# PCB_Telemetria_2020.net
KiCad netlist of a schematic drawn in EAGLE
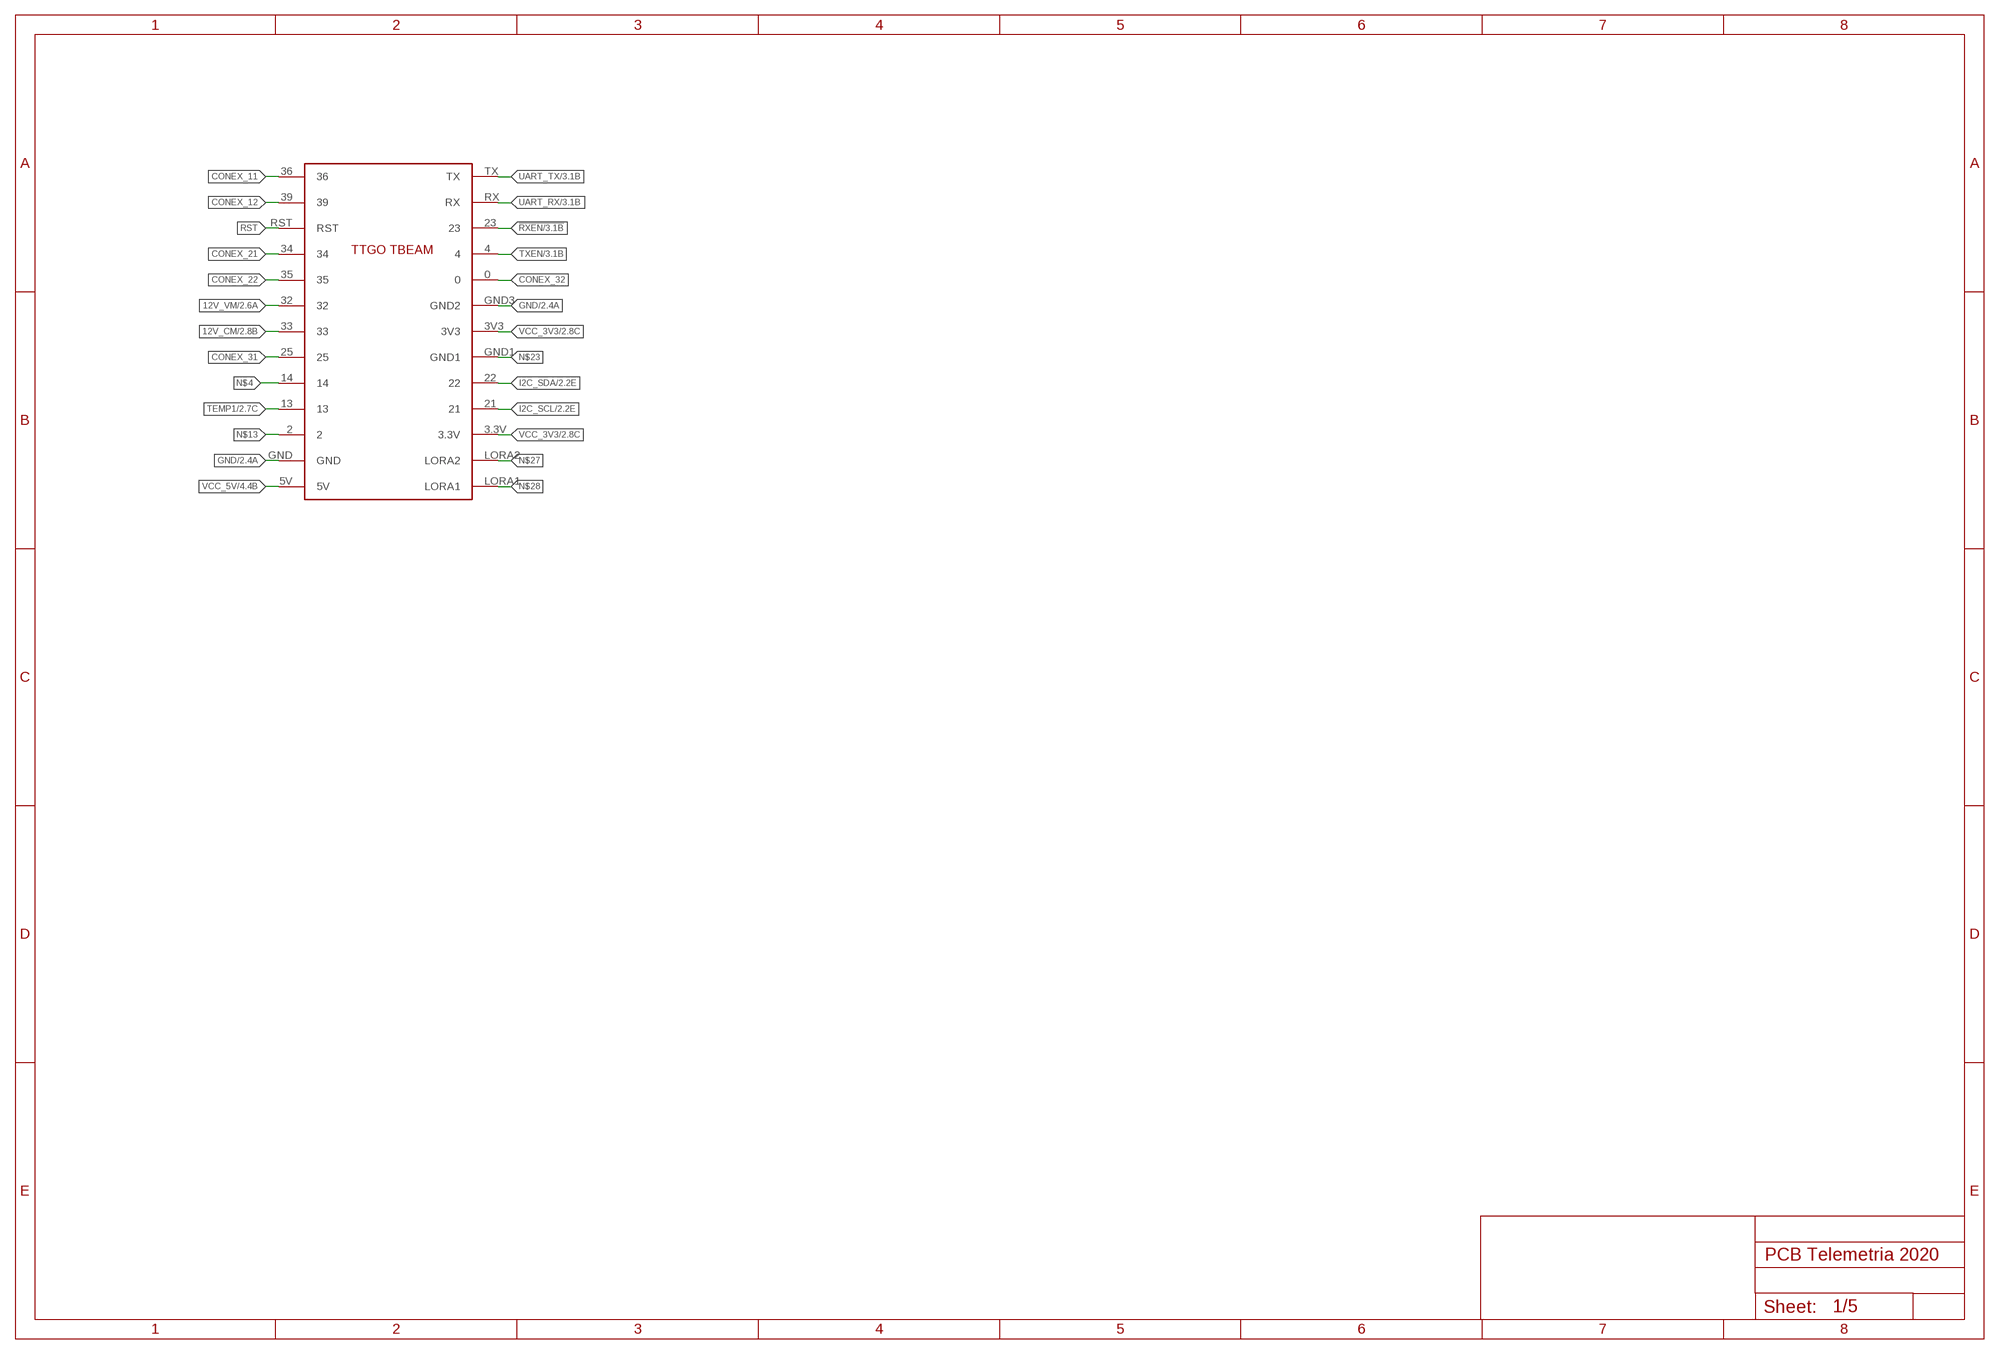
[diagram p0: schematic, sheet 1]
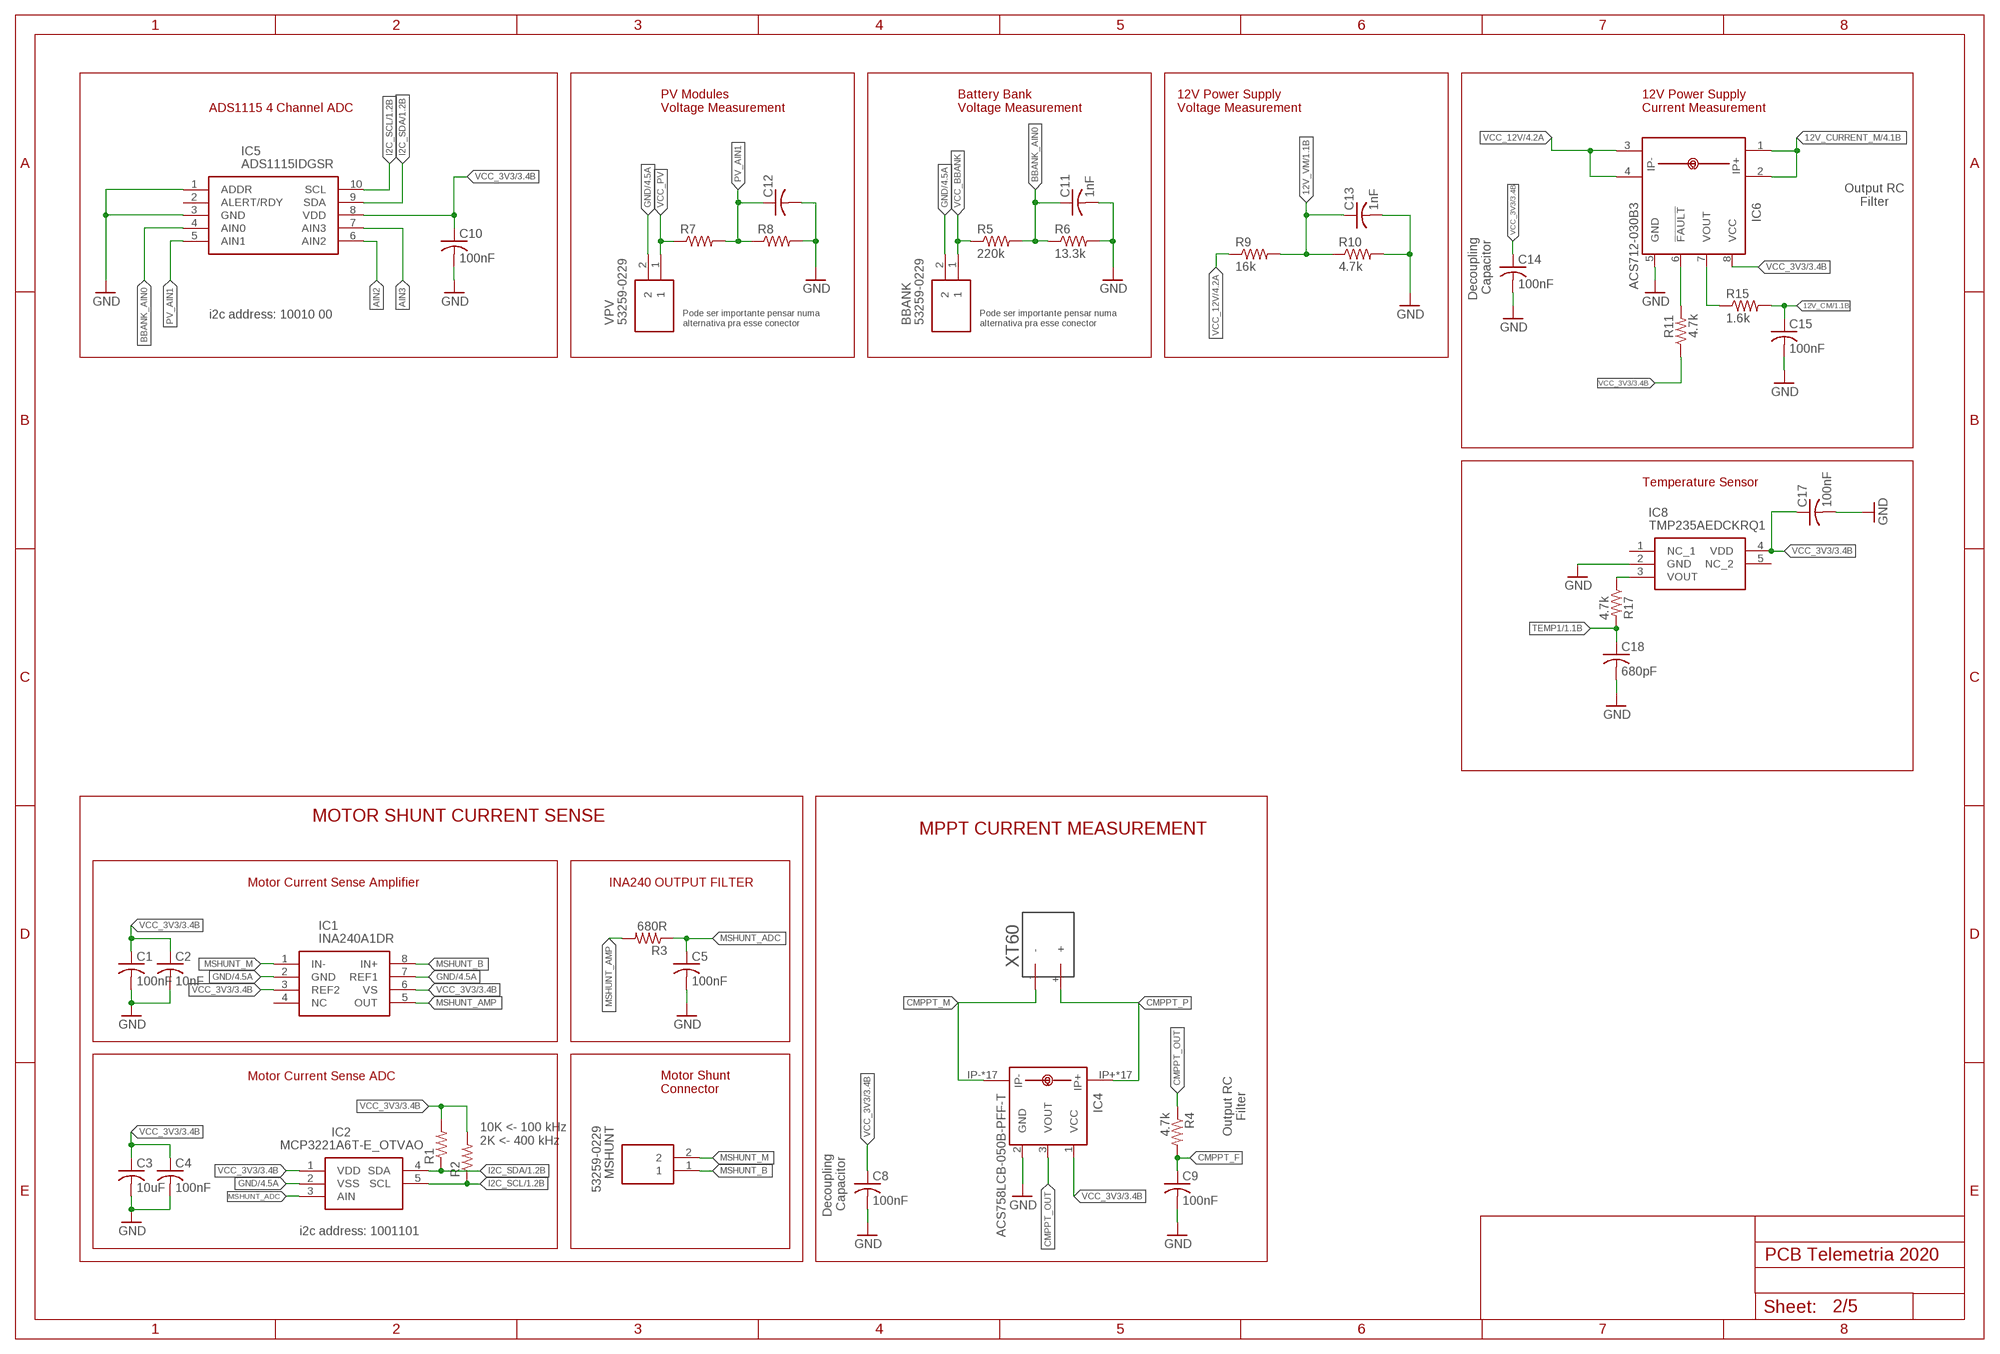
[diagram p1: schematic, sheet 2]
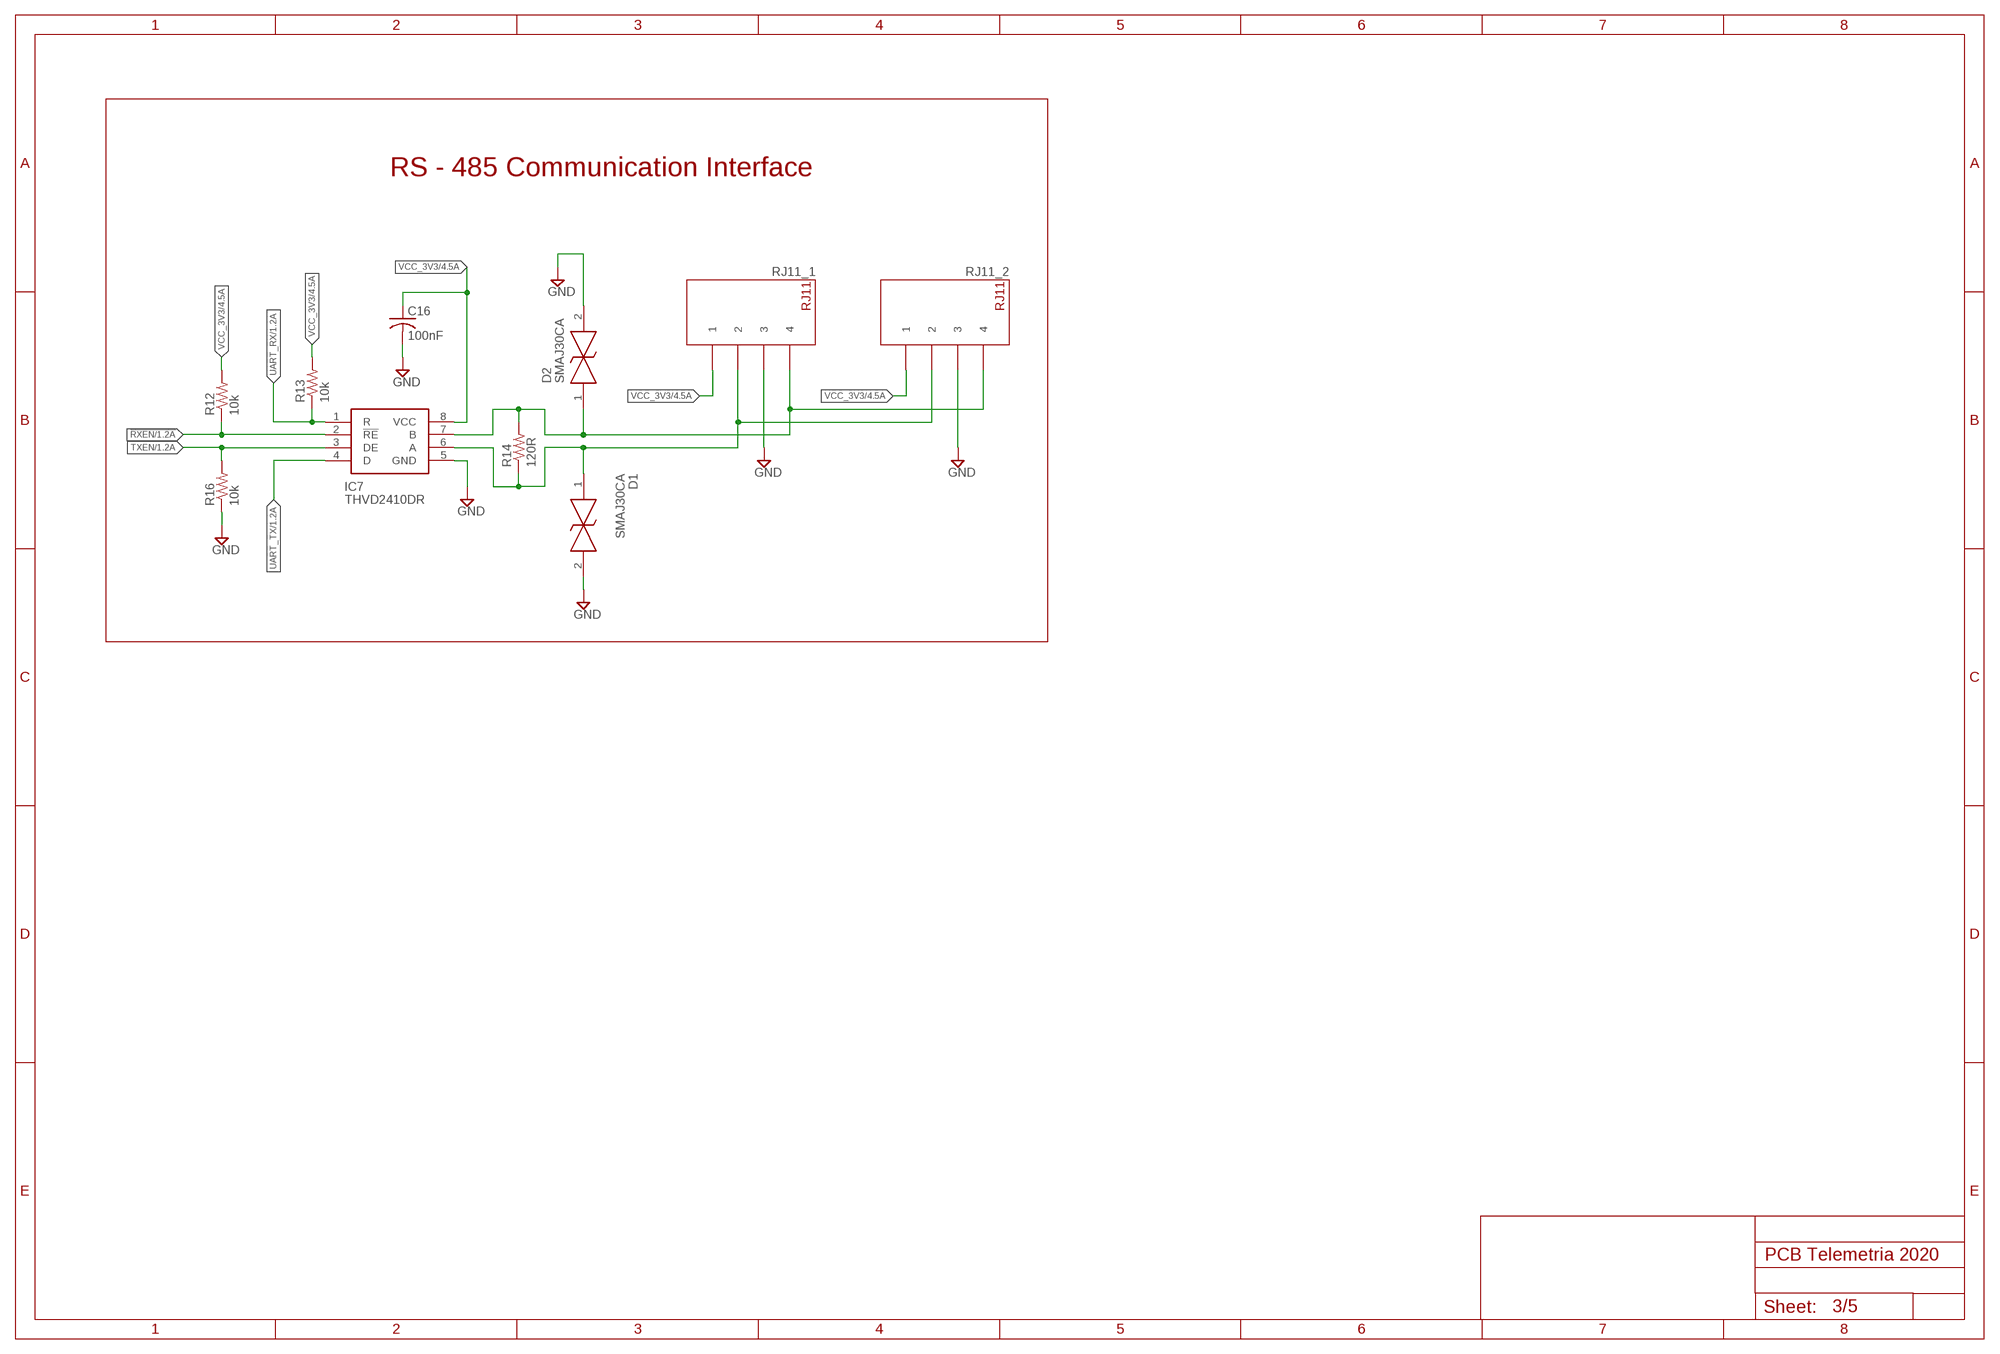
[diagram p2: schematic, sheet 3]
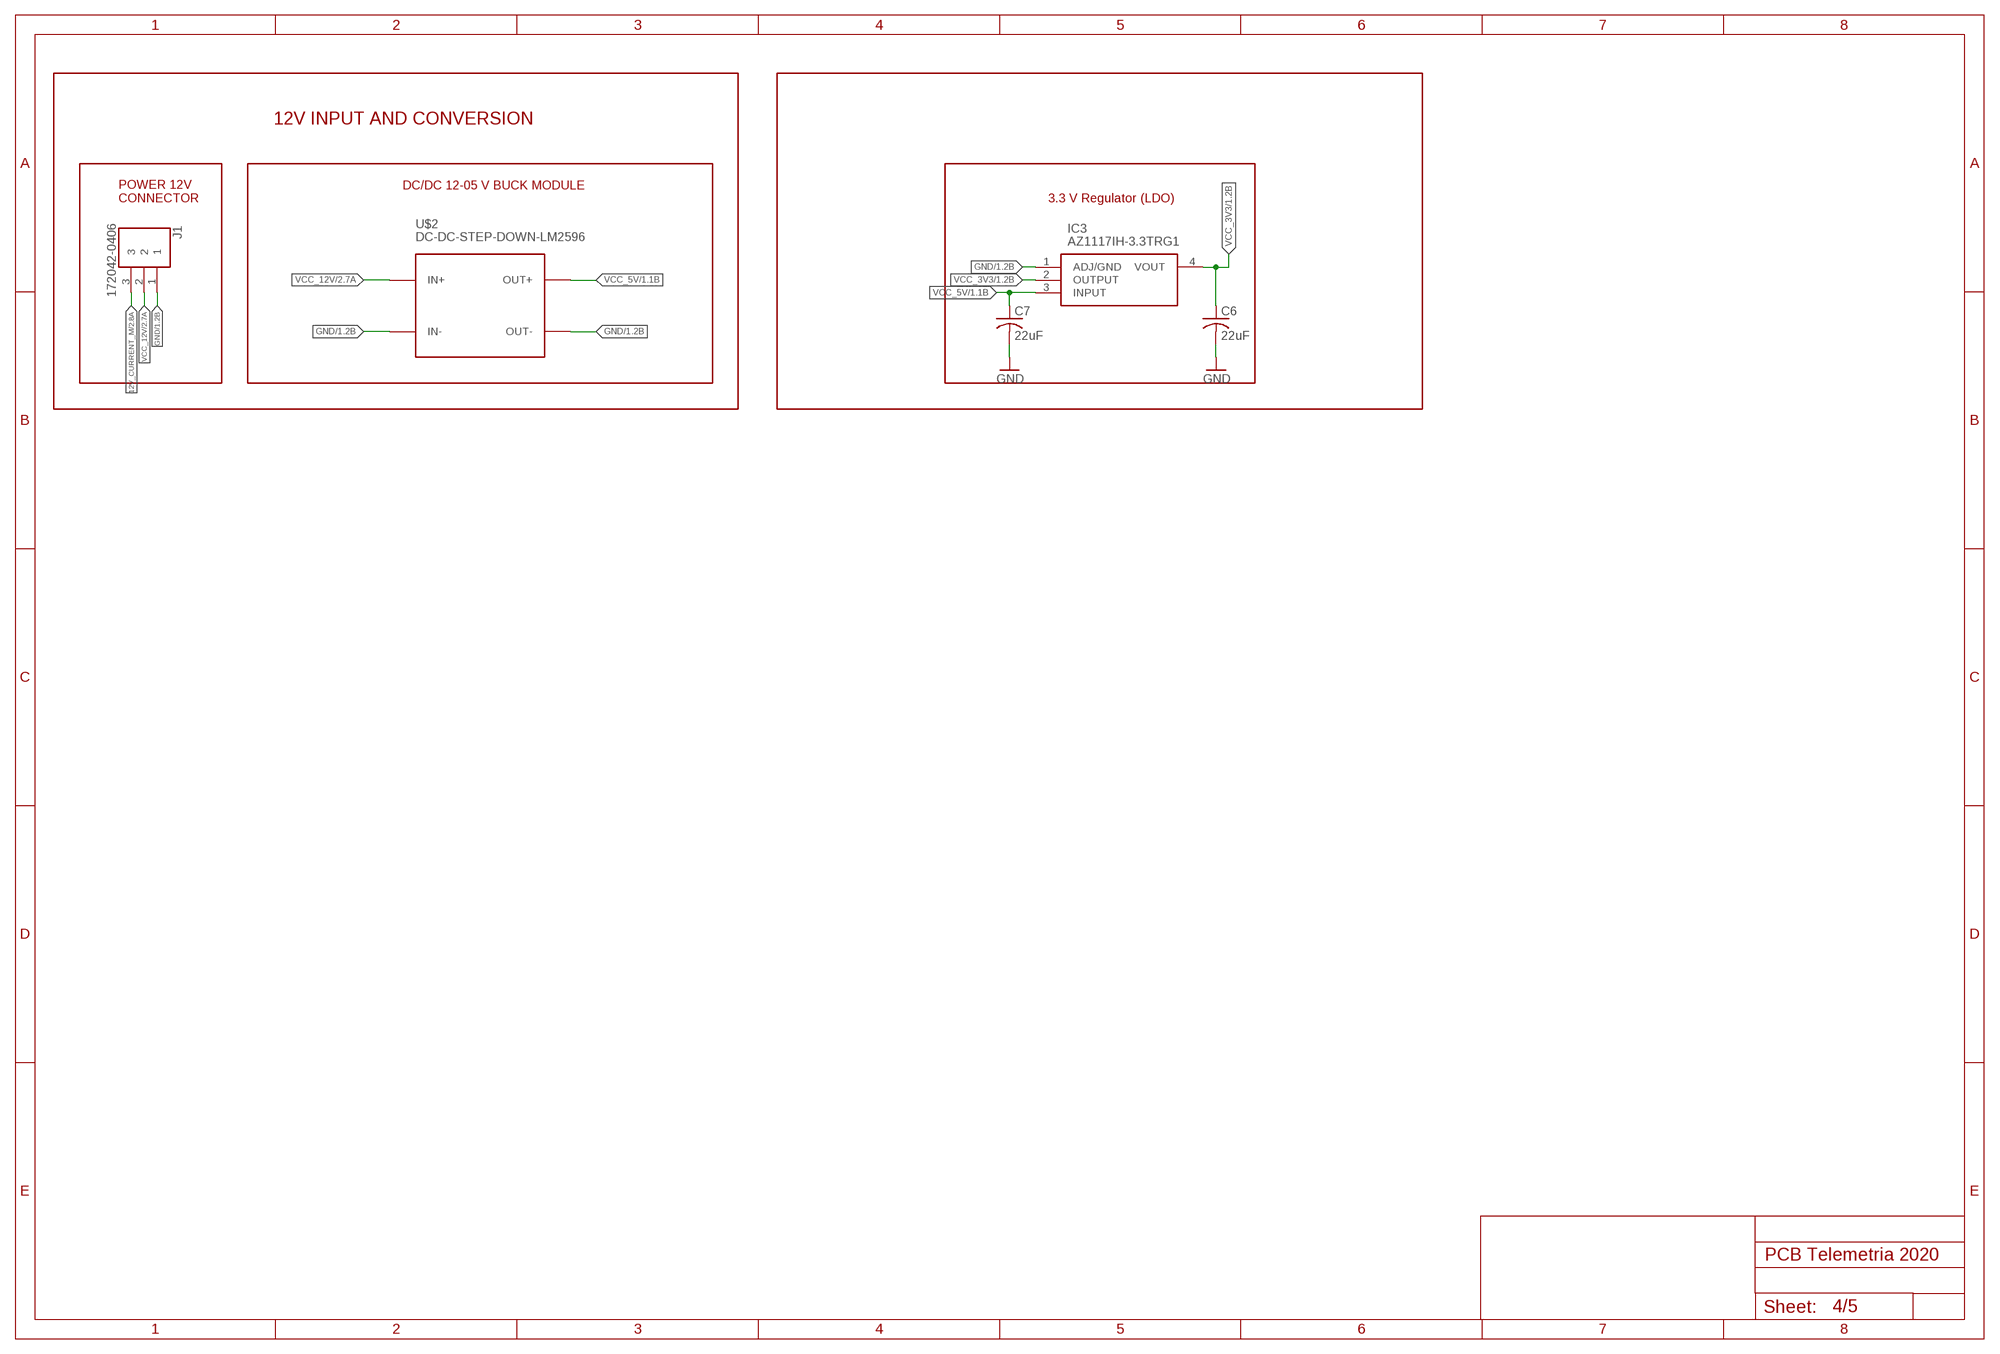
[diagram p3: schematic, sheet 4]
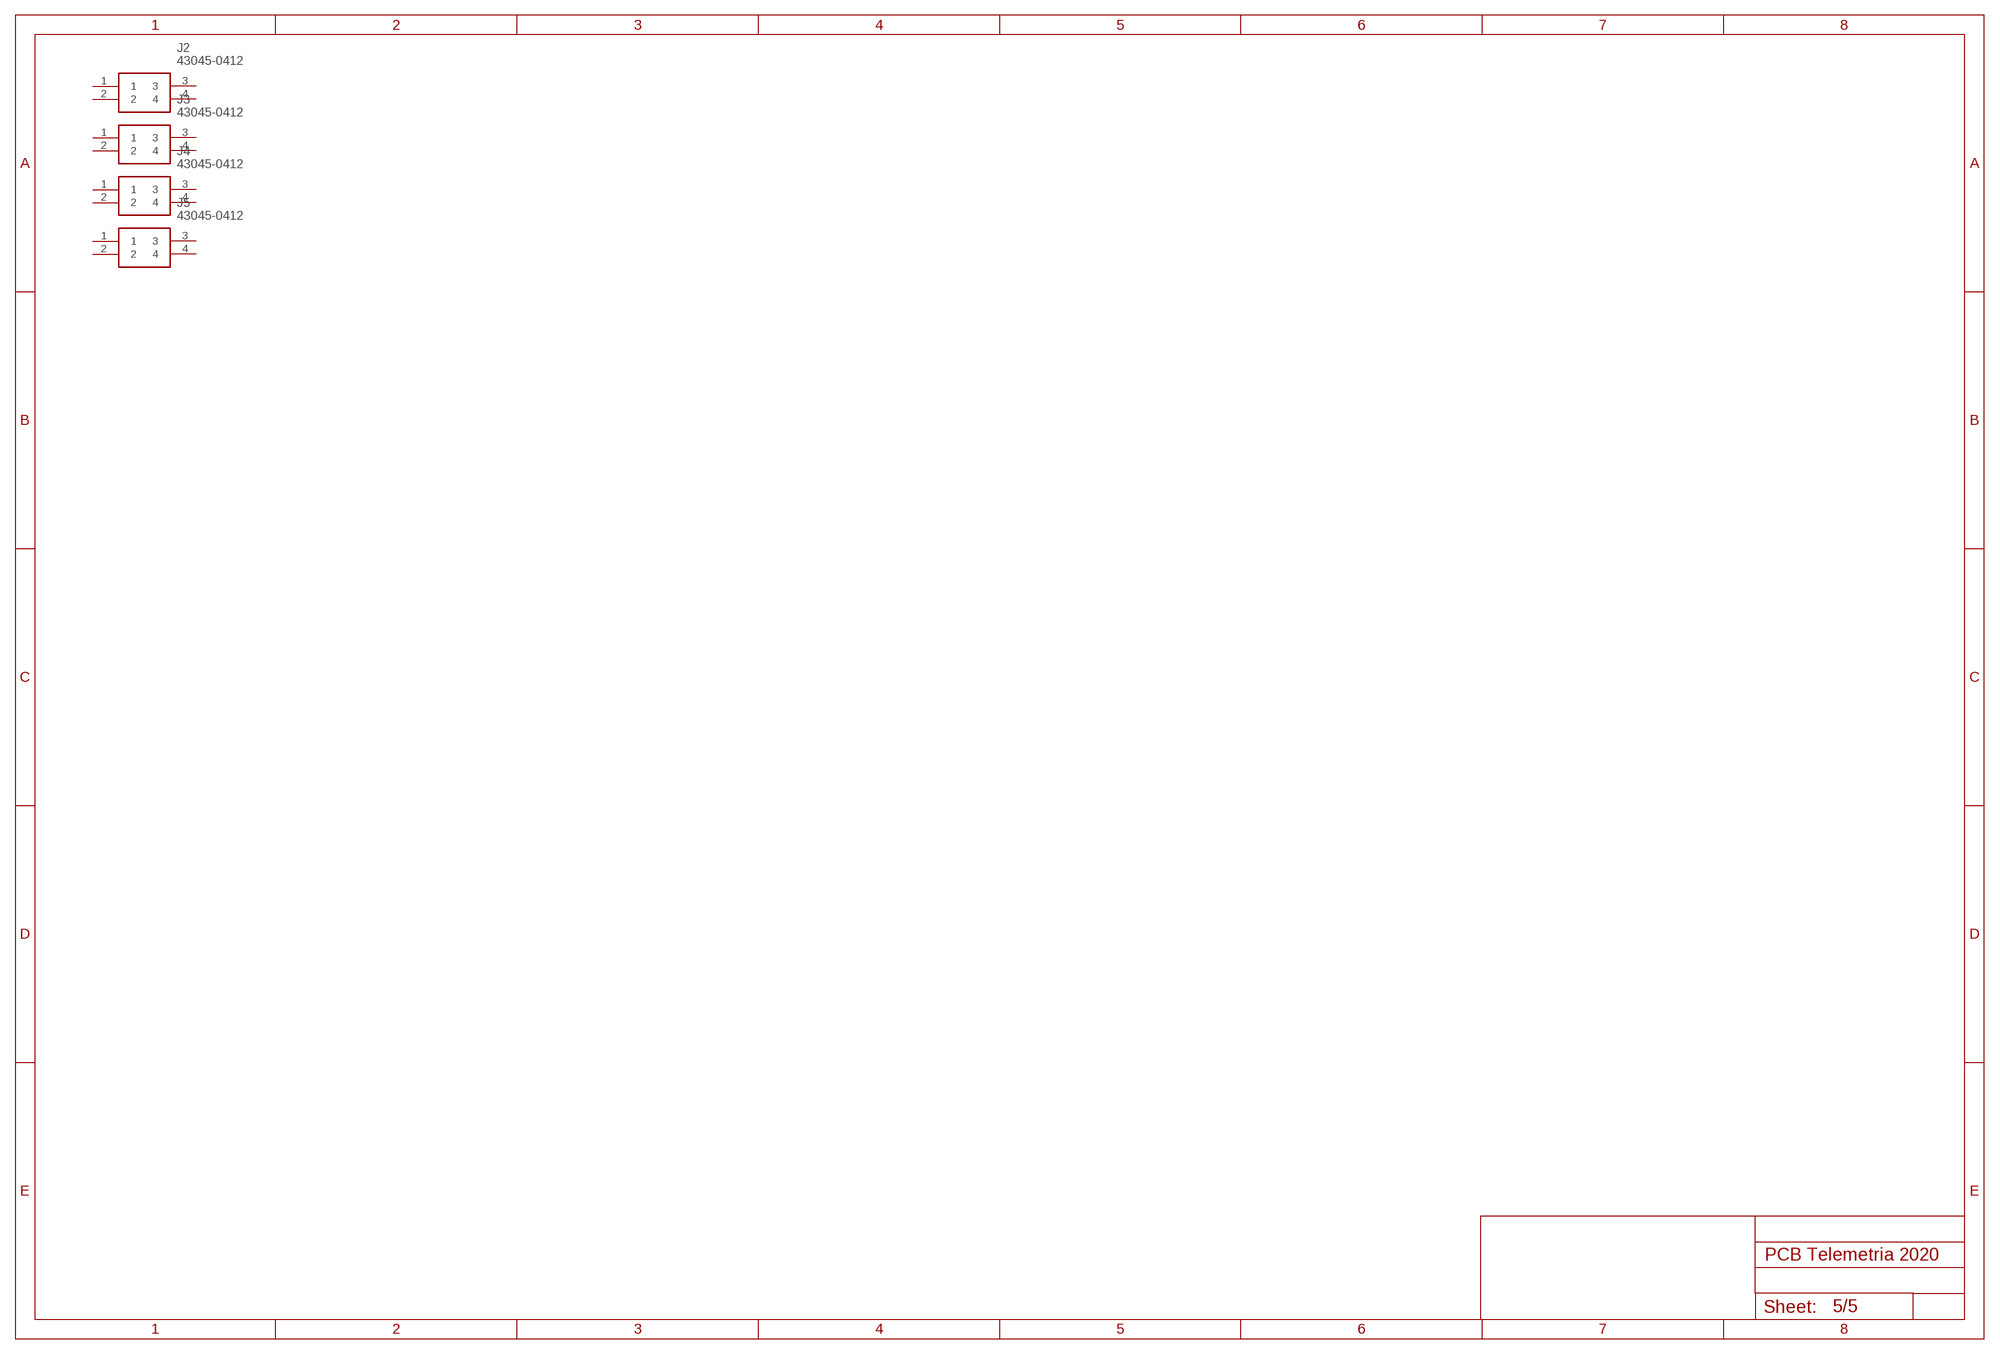
[diagram p4: schematic, sheet 5]

(export (version "E")
  (design (tool "Eeschema 10.0.6"))
  (components
    (comp (ref "C6")
      (value "22uF")
      (footprint "eagle-import:C0805")
      (libsource (lib "eagle-import") (part "C-USC0805"))
    )
    (comp (ref "C7")
      (value "22uF")
      (footprint "eagle-import:C0805")
      (libsource (lib "eagle-import") (part "C-USC0805"))
    )
    (comp (ref "IC3")
      (value "AZ1117IH-3.3TRG1")
      (footprint "eagle-import:SOT230P700X170-4N")
      (fields (field (name "MOUSER_PART_NUMBER") "621-AZ1117IH-3.3TRG1"))
      (libsource (lib "eagle-import") (part "AZ1117IH-3.3TRG1"))
    )
    (comp (ref "J1")
      (value "172042-0406")
      (footprint "eagle-import:MOLEX_172042-0406")
      (fields (field (name "MF") "Molex") (field (name "MP") "172042-0302"))
      (libsource (lib "eagle-import") (part "172042-0406"))
    )
    (comp (ref "U$2")
      (value "DC-DC-STEP-DOWN-LM2596")
      (footprint "eagle-import:DC-DC-STEP-DOWN-LM2596")
      (libsource (lib "eagle-import") (part "DC-DC-STEP-DOWN-LM2596"))
    )
    (comp (ref "BBANK")
      (value "53259-0229")
      (footprint "eagle-import:0532590229")
      (fields (field (name "MOUSER_PART_NUMBER") "538-53259-0229"))
      (libsource (lib "eagle-import") (part "53259-0229"))
    )
    (comp (ref "C1")
      (value "100nF")
      (footprint "eagle-import:C0805")
      (libsource (lib "eagle-import") (part "C-USC0805"))
    )
    (comp (ref "C2")
      (value "10nF")
      (footprint "eagle-import:C0805")
      (libsource (lib "eagle-import") (part "C-USC0805"))
    )
    (comp (ref "C3")
      (value "10uF")
      (footprint "eagle-import:C0805")
      (libsource (lib "eagle-import") (part "C-USC0805"))
    )
    (comp (ref "C4")
      (value "100nF")
      (footprint "eagle-import:C0805")
      (libsource (lib "eagle-import") (part "C-USC0805"))
    )
    (comp (ref "C5")
      (value "100nF")
      (footprint "eagle-import:C0805")
      (libsource (lib "eagle-import") (part "C-USC0805"))
    )
    (comp (ref "C8")
      (value "100nF")
      (footprint "eagle-import:C0805")
      (libsource (lib "eagle-import") (part "C-USC0805"))
    )
    (comp (ref "C9")
      (value "100nF")
      (footprint "eagle-import:C0805")
      (libsource (lib "eagle-import") (part "C-USC0805"))
    )
    (comp (ref "C10")
      (value "100nF")
      (footprint "eagle-import:C0805")
      (libsource (lib "eagle-import") (part "C-USC0805"))
    )
    (comp (ref "C11")
      (value "1nF")
      (footprint "eagle-import:C0805")
      (libsource (lib "eagle-import") (part "C-USC0805"))
    )
    (comp (ref "C12")
      (value "C-USC0805")
      (footprint "eagle-import:C0805")
      (libsource (lib "eagle-import") (part "C-USC0805"))
    )
    (comp (ref "C13")
      (value "1nF")
      (footprint "eagle-import:C0805")
      (libsource (lib "eagle-import") (part "C-USC0805"))
    )
    (comp (ref "C14")
      (value "100nF")
      (footprint "eagle-import:C0805")
      (libsource (lib "eagle-import") (part "C-USC0805"))
    )
    (comp (ref "C15")
      (value "100nF")
      (footprint "eagle-import:C0805")
      (libsource (lib "eagle-import") (part "C-USC0805"))
    )
    (comp (ref "C17")
      (value "100nF")
      (footprint "eagle-import:C0805")
      (libsource (lib "eagle-import") (part "C-USC0805"))
    )
    (comp (ref "C18")
      (value "680pF")
      (footprint "eagle-import:C0805")
      (libsource (lib "eagle-import") (part "C-USC0805"))
    )
    (comp (ref "IC1")
      (value "INA240A1DR")
      (footprint "eagle-import:SOIC127P600X175-8N")
      (fields (field (name "MOUSER_PART_NUMBER") "595-INA240A1DR"))
      (libsource (lib "eagle-import") (part "INA240A1DR"))
    )
    (comp (ref "IC2")
      (value "MCP3221A6T-E_OTVAO")
      (footprint "eagle-import:SOT95P280X145-5N")
      (fields
        (field (name "MANUFACTURER_PART_NUMBER") "MCP3221A6T-E/OTVAO")
        (field (name "MOUSER_PART_NUMBER") "579-MCP3221A6TEOTVAO")
      )
      (libsource (lib "eagle-import") (part "MCP3221A6T-E_OTVAO"))
    )
    (comp (ref "IC4")
      (value "ACS758LCB-050B-PFF-T")
      (footprint "eagle-import:CB-PFF")
      (libsource (lib "eagle-import") (part "ACS758LCB-050B-PFF-T"))
    )
    (comp (ref "IC5")
      (value "ADS1115IDGSR")
      (footprint "eagle-import:SOP50P490X110-10N")
      (fields (field (name "MOUSER_PART_NUMBER") "595-ADS1115IDGSR"))
      (libsource (lib "eagle-import") (part "ADS1115IDGSR"))
    )
    (comp (ref "IC6")
      (value "ACS712-030B3")
      (footprint "eagle-import:SOIC8")
      (libsource (lib "eagle-import") (part "ACS712-LC"))
    )
    (comp (ref "IC8")
      (value "TMP235AEDCKRQ1")
      (footprint "eagle-import:SOT65P210X110-5N")
      (fields (field (name "MOUSER_PART_NUMBER") "595-TMP235AEDCKRQ1"))
      (libsource (lib "eagle-import") (part "TMP235AEDCKRQ1"))
    )
    (comp (ref "MSHUNT")
      (value "53259-0229")
      (footprint "eagle-import:0532590229")
      (fields (field (name "MOUSER_PART_NUMBER") "538-53259-0229"))
      (libsource (lib "eagle-import") (part "53259-0229"))
    )
    (comp (ref "R1")
      (value "R-US_R0805")
      (footprint "eagle-import:R0805")
      (libsource (lib "eagle-import") (part "R-US_R0805"))
    )
    (comp (ref "R2")
      (value "R-US_R0805")
      (footprint "eagle-import:R0805")
      (libsource (lib "eagle-import") (part "R-US_R0805"))
    )
    (comp (ref "R3")
      (value "680R")
      (footprint "eagle-import:R0805")
      (libsource (lib "eagle-import") (part "R-US_R0805"))
    )
    (comp (ref "R4")
      (value "4.7k")
      (footprint "eagle-import:R0805")
      (libsource (lib "eagle-import") (part "R-US_R0805"))
    )
    (comp (ref "R5")
      (value "220k")
      (footprint "eagle-import:R0805")
      (libsource (lib "eagle-import") (part "R-US_R0805"))
    )
    (comp (ref "R6")
      (value "13.3k")
      (footprint "eagle-import:R0805")
      (libsource (lib "eagle-import") (part "R-US_R0805"))
    )
    (comp (ref "R7")
      (value "R-US_R0805")
      (footprint "eagle-import:R0805")
      (libsource (lib "eagle-import") (part "R-US_R0805"))
    )
    (comp (ref "R8")
      (value "R-US_R0805")
      (footprint "eagle-import:R0805")
      (libsource (lib "eagle-import") (part "R-US_R0805"))
    )
    (comp (ref "R9")
      (value "16k")
      (footprint "eagle-import:R0805")
      (libsource (lib "eagle-import") (part "R-US_R0805"))
    )
    (comp (ref "R10")
      (value "4.7k")
      (footprint "eagle-import:R0805")
      (libsource (lib "eagle-import") (part "R-US_R0805"))
    )
    (comp (ref "R11")
      (value "4.7k")
      (footprint "eagle-import:R0805")
      (libsource (lib "eagle-import") (part "R-US_R0805"))
    )
    (comp (ref "R15")
      (value "1.6k")
      (footprint "eagle-import:R0805")
      (libsource (lib "eagle-import") (part "R-US_R0805"))
    )
    (comp (ref "R17")
      (value "4.7k")
      (footprint "eagle-import:R0805")
      (libsource (lib "eagle-import") (part "R-US_R0805"))
    )
    (comp (ref "U$3")
      (value "XT60")
      (footprint "eagle-import:XT60")
      (libsource (lib "eagle-import") (part "XT60"))
    )
    (comp (ref "VPV")
      (value "53259-0229")
      (footprint "eagle-import:0532590229")
      (fields (field (name "MOUSER_PART_NUMBER") "538-53259-0229"))
      (libsource (lib "eagle-import") (part "53259-0229"))
    )
    (comp (ref "U$1")
      (value "TTGOBEAM")
      (footprint "eagle-import:TTGOBEAM")
      (libsource (lib "eagle-import") (part "TTGOBEAM"))
    )
    (comp (ref "C16")
      (value "100nF")
      (footprint "eagle-import:C0805")
      (libsource (lib "eagle-import") (part "C-USC0805"))
    )
    (comp (ref "D1")
      (value "SMAJ30CA")
      (footprint "eagle-import:DIONM5026X229N")
      (fields (field (name "MOUSER_PART_NUMBER") "576-SMAJ30CA"))
      (libsource (lib "eagle-import") (part "SMAJ30CA"))
    )
    (comp (ref "D2")
      (value "SMAJ30CA")
      (footprint "eagle-import:DIONM5026X229N")
      (fields (field (name "MOUSER_PART_NUMBER") "576-SMAJ30CA"))
      (libsource (lib "eagle-import") (part "SMAJ30CA"))
    )
    (comp (ref "IC7")
      (value "THVD2410DR")
      (footprint "eagle-import:SOIC127P600X175-8N")
      (fields (field (name "MOUSER_PART_NUMBER") "595-THVD2410DR"))
      (libsource (lib "eagle-import") (part "THVD2410DR"))
    )
    (comp (ref "R12")
      (value "10k")
      (footprint "eagle-import:M0805")
      (libsource (lib "eagle-import") (part "R-US_M0805"))
    )
    (comp (ref "R13")
      (value "10k")
      (footprint "eagle-import:M0805")
      (libsource (lib "eagle-import") (part "R-US_M0805"))
    )
    (comp (ref "R14")
      (value "120R")
      (footprint "eagle-import:M0805")
      (libsource (lib "eagle-import") (part "R-US_M0805"))
    )
    (comp (ref "R16")
      (value "10k")
      (footprint "eagle-import:M0805")
      (libsource (lib "eagle-import") (part "R-US_M0805"))
    )
    (comp (ref "RJ11_1")
      (value "TFC44")
      (footprint "eagle-import:TFC44")
      (libsource (lib "eagle-import") (part "TFC44"))
    )
    (comp (ref "RJ11_2")
      (value "TFC44")
      (footprint "eagle-import:TFC44")
      (libsource (lib "eagle-import") (part "TFC44"))
    )
    (comp (ref "J2")
      (value "43045-0412")
      (footprint "eagle-import:43045-0412")
      (fields (field (name "MOUSER_PART_NUMBER") "538-43045-0412"))
      (libsource (lib "eagle-import") (part "43045-0412"))
    )
    (comp (ref "J3")
      (value "43045-0412")
      (footprint "eagle-import:43045-0412")
      (fields (field (name "MOUSER_PART_NUMBER") "538-43045-0412"))
      (libsource (lib "eagle-import") (part "43045-0412"))
    )
    (comp (ref "J4")
      (value "43045-0412")
      (footprint "eagle-import:43045-0412")
      (fields (field (name "MOUSER_PART_NUMBER") "538-43045-0412"))
      (libsource (lib "eagle-import") (part "43045-0412"))
    )
    (comp (ref "J5")
      (value "43045-0412")
      (footprint "eagle-import:43045-0412")
      (fields (field (name "MOUSER_PART_NUMBER") "538-43045-0412"))
      (libsource (lib "eagle-import") (part "43045-0412"))
    )
  )
  (nets
    (net (code "1") (name "12V_CM") (class "Default")
      (node (ref "C15") (pin "1") (pinfunction "1_1") (pintype "passive"))
      (node (ref "R15") (pin "2") (pinfunction "2_2") (pintype "passive"))
      (node (ref "U$1") (pin "33") (pinfunction "33_33") (pintype "bidirectional"))
    )
    (net (code "2") (name "12V_CURRENT_M") (class "Default")
      (node (ref "IC6") (pin "1") (pinfunction "IP+_1") (pintype "passive"))
      (node (ref "IC6") (pin "2") (pinfunction "IP+1_2") (pintype "passive"))
      (node (ref "J1") (pin "3") (pinfunction "3_3") (pintype "passive"))
    )
    (net (code "3") (name "12V_VM") (class "Default")
      (node (ref "C13") (pin "1") (pinfunction "1_1") (pintype "passive"))
      (node (ref "R10") (pin "1") (pinfunction "1_1") (pintype "passive"))
      (node (ref "R9") (pin "2") (pinfunction "2_2") (pintype "passive"))
      (node (ref "U$1") (pin "32") (pinfunction "32_32") (pintype "bidirectional"))
    )
    (net (code "4") (name "AIN2") (class "Default")
      (node (ref "IC5") (pin "6") (pinfunction "AIN2_6") (pintype "bidirectional"))
    )
    (net (code "5") (name "AIN3") (class "Default")
      (node (ref "IC5") (pin "7") (pinfunction "AIN3_7") (pintype "bidirectional"))
    )
    (net (code "6") (name "BBANK_AIN0") (class "Default")
      (node (ref "C11") (pin "1") (pinfunction "1_1") (pintype "passive"))
      (node (ref "IC5") (pin "4") (pinfunction "AIN0_4") (pintype "bidirectional"))
      (node (ref "R5") (pin "2") (pinfunction "2_2") (pintype "passive"))
      (node (ref "R6") (pin "1") (pinfunction "1_1") (pintype "passive"))
    )
    (net (code "7") (name "CMPPT_F") (class "Default")
      (node (ref "C9") (pin "1") (pinfunction "1_1") (pintype "passive"))
      (node (ref "R4") (pin "2") (pinfunction "2_2") (pintype "passive"))
    )
    (net (code "8") (name "CMPPT_M") (class "Default")
      (node (ref "IC4") (pin "IP-") (pinfunction "IP-_IP-") (pintype "passive"))
      (node (ref "IC4") (pin "IP-@10") (pinfunction "IP-_IP-@10") (pintype "passive"))
      (node (ref "IC4") (pin "IP-@11") (pinfunction "IP-_IP-@11") (pintype "passive"))
      (node (ref "IC4") (pin "IP-@12") (pinfunction "IP-_IP-@12") (pintype "passive"))
      (node (ref "IC4") (pin "IP-@13") (pinfunction "IP-_IP-@13") (pintype "passive"))
      (node (ref "IC4") (pin "IP-@14") (pinfunction "IP-_IP-@14") (pintype "passive"))
      (node (ref "IC4") (pin "IP-@15") (pinfunction "IP-_IP-@15") (pintype "passive"))
      (node (ref "IC4") (pin "IP-@16") (pinfunction "IP-_IP-@16") (pintype "passive"))
      (node (ref "IC4") (pin "IP-@17") (pinfunction "IP-_IP-@17") (pintype "passive"))
      (node (ref "IC4") (pin "IP-@2") (pinfunction "IP-_IP-@2") (pintype "passive"))
      (node (ref "IC4") (pin "IP-@3") (pinfunction "IP-_IP-@3") (pintype "passive"))
      (node (ref "IC4") (pin "IP-@4") (pinfunction "IP-_IP-@4") (pintype "passive"))
      (node (ref "IC4") (pin "IP-@5") (pinfunction "IP-_IP-@5") (pintype "passive"))
      (node (ref "IC4") (pin "IP-@6") (pinfunction "IP-_IP-@6") (pintype "passive"))
      (node (ref "IC4") (pin "IP-@7") (pinfunction "IP-_IP-@7") (pintype "passive"))
      (node (ref "IC4") (pin "IP-@8") (pinfunction "IP-_IP-@8") (pintype "passive"))
      (node (ref "IC4") (pin "IP-@9") (pinfunction "IP-_IP-@9") (pintype "passive"))
      (node (ref "U$3") (pin "-") (pinfunction "-_-") (pintype "bidirectional"))
    )
    (net (code "9") (name "CMPPT_OUT") (class "Default")
      (node (ref "IC4") (pin "3") (pinfunction "VOUT_3") (pintype "output"))
      (node (ref "R4") (pin "1") (pinfunction "1_1") (pintype "passive"))
    )
    (net (code "10") (name "CMPPT_P") (class "Default")
      (node (ref "IC4") (pin "IP+") (pinfunction "IP+_IP+") (pintype "passive"))
      (node (ref "IC4") (pin "IP+@10") (pinfunction "IP+_IP+@10") (pintype "passive"))
      (node (ref "IC4") (pin "IP+@11") (pinfunction "IP+_IP+@11") (pintype "passive"))
      (node (ref "IC4") (pin "IP+@12") (pinfunction "IP+_IP+@12") (pintype "passive"))
      (node (ref "IC4") (pin "IP+@13") (pinfunction "IP+_IP+@13") (pintype "passive"))
      (node (ref "IC4") (pin "IP+@14") (pinfunction "IP+_IP+@14") (pintype "passive"))
      (node (ref "IC4") (pin "IP+@15") (pinfunction "IP+_IP+@15") (pintype "passive"))
      (node (ref "IC4") (pin "IP+@16") (pinfunction "IP+_IP+@16") (pintype "passive"))
      (node (ref "IC4") (pin "IP+@17") (pinfunction "IP+_IP+@17") (pintype "passive"))
      (node (ref "IC4") (pin "IP+@2") (pinfunction "IP+_IP+@2") (pintype "passive"))
      (node (ref "IC4") (pin "IP+@3") (pinfunction "IP+_IP+@3") (pintype "passive"))
      (node (ref "IC4") (pin "IP+@4") (pinfunction "IP+_IP+@4") (pintype "passive"))
      (node (ref "IC4") (pin "IP+@5") (pinfunction "IP+_IP+@5") (pintype "passive"))
      (node (ref "IC4") (pin "IP+@6") (pinfunction "IP+_IP+@6") (pintype "passive"))
      (node (ref "IC4") (pin "IP+@7") (pinfunction "IP+_IP+@7") (pintype "passive"))
      (node (ref "IC4") (pin "IP+@8") (pinfunction "IP+_IP+@8") (pintype "passive"))
      (node (ref "IC4") (pin "IP+@9") (pinfunction "IP+_IP+@9") (pintype "passive"))
      (node (ref "U$3") (pin "+") (pinfunction "+_+") (pintype "bidirectional"))
    )
    (net (code "11") (name "CONEX_11") (class "Default")
      (node (ref "U$1") (pin "36") (pinfunction "36_36") (pintype "bidirectional"))
    )
    (net (code "12") (name "CONEX_12") (class "Default")
      (node (ref "U$1") (pin "39") (pinfunction "39_39") (pintype "bidirectional"))
    )
    (net (code "13") (name "CONEX_21") (class "Default")
      (node (ref "U$1") (pin "34") (pinfunction "34_34") (pintype "bidirectional"))
    )
    (net (code "14") (name "CONEX_22") (class "Default")
      (node (ref "U$1") (pin "35") (pinfunction "35_35") (pintype "bidirectional"))
    )
    (net (code "15") (name "CONEX_31") (class "Default")
      (node (ref "U$1") (pin "25") (pinfunction "25_25") (pintype "bidirectional"))
    )
    (net (code "16") (name "CONEX_32") (class "Default")
      (node (ref "U$1") (pin "0") (pinfunction "0_0") (pintype "bidirectional"))
    )
    (net (code "17") (name "GND") (class "Default")
      (node (ref "BBANK") (pin "2") (pinfunction "2_2") (pintype "bidirectional"))
      (node (ref "C1") (pin "2") (pinfunction "2_2") (pintype "passive"))
      (node (ref "C10") (pin "2") (pinfunction "2_2") (pintype "passive"))
      (node (ref "C11") (pin "2") (pinfunction "2_2") (pintype "passive"))
      (node (ref "C12") (pin "2") (pinfunction "2_2") (pintype "passive"))
      (node (ref "C13") (pin "2") (pinfunction "2_2") (pintype "passive"))
      (node (ref "C14") (pin "2") (pinfunction "2_2") (pintype "passive"))
      (node (ref "C15") (pin "2") (pinfunction "2_2") (pintype "passive"))
      (node (ref "C16") (pin "2") (pinfunction "2_2") (pintype "passive"))
      (node (ref "C17") (pin "2") (pinfunction "2_2") (pintype "passive"))
      (node (ref "C18") (pin "2") (pinfunction "2_2") (pintype "passive"))
      (node (ref "C2") (pin "2") (pinfunction "2_2") (pintype "passive"))
      (node (ref "C3") (pin "2") (pinfunction "2_2") (pintype "passive"))
      (node (ref "C4") (pin "2") (pinfunction "2_2") (pintype "passive"))
      (node (ref "C5") (pin "2") (pinfunction "2_2") (pintype "passive"))
      (node (ref "C6") (pin "2") (pinfunction "2_2") (pintype "passive"))
      (node (ref "C7") (pin "2") (pinfunction "2_2") (pintype "passive"))
      (node (ref "C8") (pin "2") (pinfunction "2_2") (pintype "passive"))
      (node (ref "C9") (pin "2") (pinfunction "2_2") (pintype "passive"))
      (node (ref "D1") (pin "2") (pinfunction "2_2") (pintype "bidirectional"))
      (node (ref "D2") (pin "2") (pinfunction "2_2") (pintype "bidirectional"))
      (node (ref "IC1") (pin "2") (pinfunction "GND_2") (pintype "bidirectional"))
      (node (ref "IC1") (pin "7") (pinfunction "REF1_7") (pintype "bidirectional"))
      (node (ref "IC2") (pin "2") (pinfunction "VSS_2") (pintype "bidirectional"))
      (node (ref "IC3") (pin "1") (pinfunction "ADJ/GND_1") (pintype "bidirectional"))
      (node (ref "IC4") (pin "2") (pinfunction "GND_2") (pintype "power_in"))
      (node (ref "IC5") (pin "1") (pinfunction "ADDR_1") (pintype "bidirectional"))
      (node (ref "IC5") (pin "3") (pinfunction "GND_3") (pintype "bidirectional"))
      (node (ref "IC6") (pin "5") (pinfunction "GND_5") (pintype "power_in"))
      (node (ref "IC7") (pin "5") (pinfunction "GND_5") (pintype "bidirectional"))
      (node (ref "IC8") (pin "2") (pinfunction "GND_2") (pintype "bidirectional"))
      (node (ref "J1") (pin "1") (pinfunction "1_1") (pintype "passive"))
      (node (ref "R10") (pin "2") (pinfunction "2_2") (pintype "passive"))
      (node (ref "R16") (pin "1") (pinfunction "1_1") (pintype "passive"))
      (node (ref "R6") (pin "2") (pinfunction "2_2") (pintype "passive"))
      (node (ref "R8") (pin "2") (pinfunction "2_2") (pintype "passive"))
      (node (ref "RJ11_1") (pin "P$3") (pinfunction "3_P$3") (pintype "bidirectional"))
      (node (ref "RJ11_2") (pin "P$3") (pinfunction "3_P$3") (pintype "bidirectional"))
      (node (ref "U$1") (pin "GND") (pinfunction "GND_GND") (pintype "bidirectional"))
      (node (ref "U$1") (pin "GND3") (pinfunction "GND2_GND3") (pintype "bidirectional"))
      (node (ref "U$2") (pin "IN-") (pinfunction "IN-_IN-") (pintype "bidirectional"))
      (node (ref "U$2") (pin "OUT-") (pinfunction "OUT-_OUT-") (pintype "bidirectional"))
      (node (ref "VPV") (pin "2") (pinfunction "2_2") (pintype "bidirectional"))
    )
    (net (code "18") (name "I2C_SCL") (class "Default")
      (node (ref "IC2") (pin "5") (pinfunction "SCL_5") (pintype "bidirectional"))
      (node (ref "IC5") (pin "10") (pinfunction "SCL_10") (pintype "bidirectional"))
      (node (ref "R2") (pin "1") (pinfunction "1_1") (pintype "passive"))
      (node (ref "U$1") (pin "21") (pinfunction "21_21") (pintype "bidirectional"))
    )
    (net (code "19") (name "I2C_SDA") (class "Default")
      (node (ref "IC2") (pin "4") (pinfunction "SDA_4") (pintype "bidirectional"))
      (node (ref "IC5") (pin "9") (pinfunction "SDA_9") (pintype "bidirectional"))
      (node (ref "R1") (pin "1") (pinfunction "1_1") (pintype "passive"))
      (node (ref "U$1") (pin "22") (pinfunction "22_22") (pintype "bidirectional"))
    )
    (net (code "20") (name "MSHUNT_ADC") (class "Default")
      (node (ref "C5") (pin "1") (pinfunction "1_1") (pintype "passive"))
      (node (ref "IC2") (pin "3") (pinfunction "AIN_3") (pintype "bidirectional"))
      (node (ref "R3") (pin "1") (pinfunction "1_1") (pintype "passive"))
    )
    (net (code "21") (name "MSHUNT_AMP") (class "Default")
      (node (ref "IC1") (pin "5") (pinfunction "OUT_5") (pintype "bidirectional"))
      (node (ref "R3") (pin "2") (pinfunction "2_2") (pintype "passive"))
    )
    (net (code "22") (name "MSHUNT_B") (class "Default")
      (node (ref "IC1") (pin "8") (pinfunction "IN+_8") (pintype "bidirectional"))
      (node (ref "MSHUNT") (pin "1") (pinfunction "1_1") (pintype "bidirectional"))
    )
    (net (code "23") (name "MSHUNT_M") (class "Default")
      (node (ref "IC1") (pin "1") (pinfunction "IN-_1") (pintype "bidirectional"))
      (node (ref "MSHUNT") (pin "2") (pinfunction "2_2") (pintype "bidirectional"))
    )
    (net (code "24") (name "N$4") (class "Default")
      (node (ref "U$1") (pin "14") (pinfunction "14_14") (pintype "bidirectional"))
    )
    (net (code "25") (name "N$13") (class "Default")
      (node (ref "U$1") (pin "2") (pinfunction "2_2") (pintype "bidirectional"))
    )
    (net (code "26") (name "N$23") (class "Default")
      (node (ref "U$1") (pin "GND1") (pinfunction "GND1_GND1") (pintype "bidirectional"))
    )
    (net (code "27") (name "N$27") (class "Default")
      (node (ref "U$1") (pin "LORA2") (pinfunction "LORA2_LORA2") (pintype "bidirectional"))
    )
    (net (code "28") (name "N$28") (class "Default")
      (node (ref "U$1") (pin "LORA1") (pinfunction "LORA1_LORA1") (pintype "bidirectional"))
    )
    (net (code "29") (name "Net-(IC6-VOUT)") (class "Default")
      (node (ref "IC6") (pin "7") (pinfunction "VOUT_7") (pintype "output"))
      (node (ref "R15") (pin "1") (pinfunction "1_1") (pintype "passive"))
    )
    (net (code "30") (name "Net-(IC6-~{FAULT})") (class "Default")
      (node (ref "IC6") (pin "6") (pinfunction "~{FAULT}_6") (pintype "bidirectional"))
      (node (ref "R11") (pin "2") (pinfunction "2_2") (pintype "passive"))
    )
    (net (code "31") (name "Net-(IC7-A)") (class "Default")
      (node (ref "D1") (pin "1") (pinfunction "1_1") (pintype "bidirectional"))
      (node (ref "IC7") (pin "6") (pinfunction "A_6") (pintype "bidirectional"))
      (node (ref "R14") (pin "1") (pinfunction "1_1") (pintype "passive"))
      (node (ref "RJ11_1") (pin "P$2") (pinfunction "2_P$2") (pintype "bidirectional"))
      (node (ref "RJ11_2") (pin "P$2") (pinfunction "2_P$2") (pintype "bidirectional"))
    )
    (net (code "32") (name "Net-(IC7-B)") (class "Default")
      (node (ref "D2") (pin "1") (pinfunction "1_1") (pintype "bidirectional"))
      (node (ref "IC7") (pin "7") (pinfunction "B_7") (pintype "bidirectional"))
      (node (ref "R14") (pin "2") (pinfunction "2_2") (pintype "passive"))
      (node (ref "RJ11_1") (pin "P$4") (pinfunction "4_P$4") (pintype "bidirectional"))
      (node (ref "RJ11_2") (pin "P$4") (pinfunction "4_P$4") (pintype "bidirectional"))
    )
    (net (code "33") (name "Net-(IC8-VOUT)") (class "Default")
      (node (ref "IC8") (pin "3") (pinfunction "VOUT_3") (pintype "bidirectional"))
      (node (ref "R17") (pin "1") (pinfunction "1_1") (pintype "passive"))
    )
    (net (code "34") (name "PV_AIN1") (class "Default")
      (node (ref "C12") (pin "1") (pinfunction "1_1") (pintype "passive"))
      (node (ref "IC5") (pin "5") (pinfunction "AIN1_5") (pintype "bidirectional"))
      (node (ref "R7") (pin "2") (pinfunction "2_2") (pintype "passive"))
      (node (ref "R8") (pin "1") (pinfunction "1_1") (pintype "passive"))
    )
    (net (code "35") (name "RST") (class "Default")
      (node (ref "U$1") (pin "RST") (pinfunction "RST_RST") (pintype "bidirectional"))
    )
    (net (code "36") (name "TEMP1") (class "Default")
      (node (ref "C18") (pin "1") (pinfunction "1_1") (pintype "passive"))
      (node (ref "R17") (pin "2") (pinfunction "2_2") (pintype "passive"))
      (node (ref "U$1") (pin "13") (pinfunction "13_13") (pintype "bidirectional"))
    )
    (net (code "37") (name "TXEN") (class "Default")
      (node (ref "IC7") (pin "3") (pinfunction "DE_3") (pintype "bidirectional"))
      (node (ref "R16") (pin "2") (pinfunction "2_2") (pintype "passive"))
      (node (ref "U$1") (pin "4") (pinfunction "4_4") (pintype "bidirectional"))
    )
    (net (code "38") (name "UART_RX") (class "Default")
      (node (ref "IC7") (pin "1") (pinfunction "R_1") (pintype "bidirectional"))
      (node (ref "R13") (pin "1") (pinfunction "1_1") (pintype "passive"))
      (node (ref "U$1") (pin "RX") (pinfunction "RX_RX") (pintype "bidirectional"))
    )
    (net (code "39") (name "UART_TX") (class "Default")
      (node (ref "IC7") (pin "4") (pinfunction "D_4") (pintype "bidirectional"))
      (node (ref "U$1") (pin "TX") (pinfunction "TX_TX") (pintype "bidirectional"))
    )
    (net (code "40") (name "VCC_3V3") (class "Default")
      (node (ref "C1") (pin "1") (pinfunction "1_1") (pintype "passive"))
      (node (ref "C10") (pin "1") (pinfunction "1_1") (pintype "passive"))
      (node (ref "C14") (pin "1") (pinfunction "1_1") (pintype "passive"))
      (node (ref "C16") (pin "1") (pinfunction "1_1") (pintype "passive"))
      (node (ref "C17") (pin "1") (pinfunction "1_1") (pintype "passive"))
      (node (ref "C2") (pin "1") (pinfunction "1_1") (pintype "passive"))
      (node (ref "C3") (pin "1") (pinfunction "1_1") (pintype "passive"))
      (node (ref "C4") (pin "1") (pinfunction "1_1") (pintype "passive"))
      (node (ref "C6") (pin "1") (pinfunction "1_1") (pintype "passive"))
      (node (ref "C8") (pin "1") (pinfunction "1_1") (pintype "passive"))
      (node (ref "IC1") (pin "3") (pinfunction "REF2_3") (pintype "bidirectional"))
      (node (ref "IC1") (pin "6") (pinfunction "VS_6") (pintype "bidirectional"))
      (node (ref "IC2") (pin "1") (pinfunction "VDD_1") (pintype "bidirectional"))
      (node (ref "IC3") (pin "2") (pinfunction "OUTPUT_2") (pintype "bidirectional"))
      (node (ref "IC3") (pin "4") (pinfunction "VOUT_4") (pintype "bidirectional"))
      (node (ref "IC4") (pin "1") (pinfunction "VCC_1") (pintype "power_in"))
      (node (ref "IC5") (pin "8") (pinfunction "VDD_8") (pintype "bidirectional"))
      (node (ref "IC6") (pin "8") (pinfunction "VCC_8") (pintype "power_in"))
      (node (ref "IC7") (pin "8") (pinfunction "VCC_8") (pintype "bidirectional"))
      (node (ref "IC8") (pin "4") (pinfunction "VDD_4") (pintype "bidirectional"))
      (node (ref "R1") (pin "2") (pinfunction "2_2") (pintype "passive"))
      (node (ref "R11") (pin "1") (pinfunction "1_1") (pintype "passive"))
      (node (ref "R12") (pin "2") (pinfunction "2_2") (pintype "passive"))
      (node (ref "R13") (pin "2") (pinfunction "2_2") (pintype "passive"))
      (node (ref "R2") (pin "2") (pinfunction "2_2") (pintype "passive"))
      (node (ref "RJ11_1") (pin "P$1") (pinfunction "1_P$1") (pintype "bidirectional"))
      (node (ref "RJ11_2") (pin "P$1") (pinfunction "1_P$1") (pintype "bidirectional"))
      (node (ref "U$1") (pin "3.3V") (pinfunction "3.3V_3.3V") (pintype "bidirectional"))
      (node (ref "U$1") (pin "3V3") (pinfunction "3V3_3V3") (pintype "bidirectional"))
    )
    (net (code "41") (name "VCC_5V") (class "Default")
      (node (ref "C7") (pin "1") (pinfunction "1_1") (pintype "passive"))
      (node (ref "IC3") (pin "3") (pinfunction "INPUT_3") (pintype "bidirectional"))
      (node (ref "U$1") (pin "5V") (pinfunction "5V_5V") (pintype "bidirectional"))
      (node (ref "U$2") (pin "OUT+") (pinfunction "OUT+_OUT+") (pintype "bidirectional"))
    )
    (net (code "42") (name "VCC_12V") (class "Default")
      (node (ref "IC6") (pin "3") (pinfunction "IP-_3") (pintype "passive"))
      (node (ref "IC6") (pin "4") (pinfunction "IP-1_4") (pintype "passive"))
      (node (ref "J1") (pin "2") (pinfunction "2_2") (pintype "passive"))
      (node (ref "R9") (pin "1") (pinfunction "1_1") (pintype "passive"))
      (node (ref "U$2") (pin "IN+") (pinfunction "IN+_IN+") (pintype "bidirectional"))
    )
    (net (code "43") (name "VCC_BBANK") (class "Default")
      (node (ref "BBANK") (pin "1") (pinfunction "1_1") (pintype "bidirectional"))
      (node (ref "R5") (pin "1") (pinfunction "1_1") (pintype "passive"))
    )
    (net (code "44") (name "VCC_PV") (class "Default")
      (node (ref "R7") (pin "1") (pinfunction "1_1") (pintype "passive"))
      (node (ref "VPV") (pin "1") (pinfunction "1_1") (pintype "bidirectional"))
    )
    (net (code "45") (name "unconnected-(IC1-NC-Pad4)") (class "Default")
      (node (ref "IC1") (pin "4") (pinfunction "NC_4") (pintype "no_connect"))
    )
    (net (code "46") (name "unconnected-(IC5-ALERT{slash}RDY-Pad2)") (class "Default")
      (node (ref "IC5") (pin "2") (pinfunction "ALERT/RDY_2") (pintype "bidirectional"))
    )
    (net (code "47") (name "unconnected-(IC8-NC_1-Pad1)") (class "Default")
      (node (ref "IC8") (pin "1") (pinfunction "NC_1_1") (pintype "bidirectional"))
    )
    (net (code "48") (name "unconnected-(IC8-NC_2-Pad5)") (class "Default")
      (node (ref "IC8") (pin "5") (pinfunction "NC_2_5") (pintype "bidirectional"))
    )
    (net (code "49") (name "unconnected-(J2-Pad1)") (class "Default")
      (node (ref "J2") (pin "1") (pinfunction "1_1") (pintype "bidirectional"))
    )
    (net (code "50") (name "unconnected-(J2-Pad2)") (class "Default")
      (node (ref "J2") (pin "2") (pinfunction "2_2") (pintype "bidirectional"))
    )
    (net (code "51") (name "unconnected-(J2-Pad3)") (class "Default")
      (node (ref "J2") (pin "3") (pinfunction "3_3") (pintype "bidirectional"))
    )
    (net (code "52") (name "unconnected-(J2-Pad4)") (class "Default")
      (node (ref "J2") (pin "4") (pinfunction "4_4") (pintype "bidirectional"))
    )
    (net (code "53") (name "unconnected-(J3-Pad1)") (class "Default")
      (node (ref "J3") (pin "1") (pinfunction "1_1") (pintype "bidirectional"))
    )
    (net (code "54") (name "unconnected-(J3-Pad2)") (class "Default")
      (node (ref "J3") (pin "2") (pinfunction "2_2") (pintype "bidirectional"))
    )
    (net (code "55") (name "unconnected-(J3-Pad3)") (class "Default")
      (node (ref "J3") (pin "3") (pinfunction "3_3") (pintype "bidirectional"))
    )
    (net (code "56") (name "unconnected-(J3-Pad4)") (class "Default")
      (node (ref "J3") (pin "4") (pinfunction "4_4") (pintype "bidirectional"))
    )
    (net (code "57") (name "unconnected-(J4-Pad1)") (class "Default")
      (node (ref "J4") (pin "1") (pinfunction "1_1") (pintype "bidirectional"))
    )
    (net (code "58") (name "unconnected-(J4-Pad2)") (class "Default")
      (node (ref "J4") (pin "2") (pinfunction "2_2") (pintype "bidirectional"))
    )
    (net (code "59") (name "unconnected-(J4-Pad3)") (class "Default")
      (node (ref "J4") (pin "3") (pinfunction "3_3") (pintype "bidirectional"))
    )
    (net (code "60") (name "unconnected-(J4-Pad4)") (class "Default")
      (node (ref "J4") (pin "4") (pinfunction "4_4") (pintype "bidirectional"))
    )
    (net (code "61") (name "unconnected-(J5-Pad1)") (class "Default")
      (node (ref "J5") (pin "1") (pinfunction "1_1") (pintype "bidirectional"))
    )
    (net (code "62") (name "unconnected-(J5-Pad2)") (class "Default")
      (node (ref "J5") (pin "2") (pinfunction "2_2") (pintype "bidirectional"))
    )
    (net (code "63") (name "unconnected-(J5-Pad3)") (class "Default")
      (node (ref "J5") (pin "3") (pinfunction "3_3") (pintype "bidirectional"))
    )
    (net (code "64") (name "unconnected-(J5-Pad4)") (class "Default")
      (node (ref "J5") (pin "4") (pinfunction "4_4") (pintype "bidirectional"))
    )
    (net (code "65") (name "~{RXEN}") (class "Default")
      (node (ref "IC7") (pin "2") (pinfunction "~{RE}_2") (pintype "bidirectional"))
      (node (ref "R12") (pin "1") (pinfunction "1_1") (pintype "passive"))
      (node (ref "U$1") (pin "23") (pinfunction "23_23") (pintype "bidirectional"))
    )
  )
)
